# NODEMCU_ESP12.net
KiCad netlist of a schematic drawn in Altium Designer
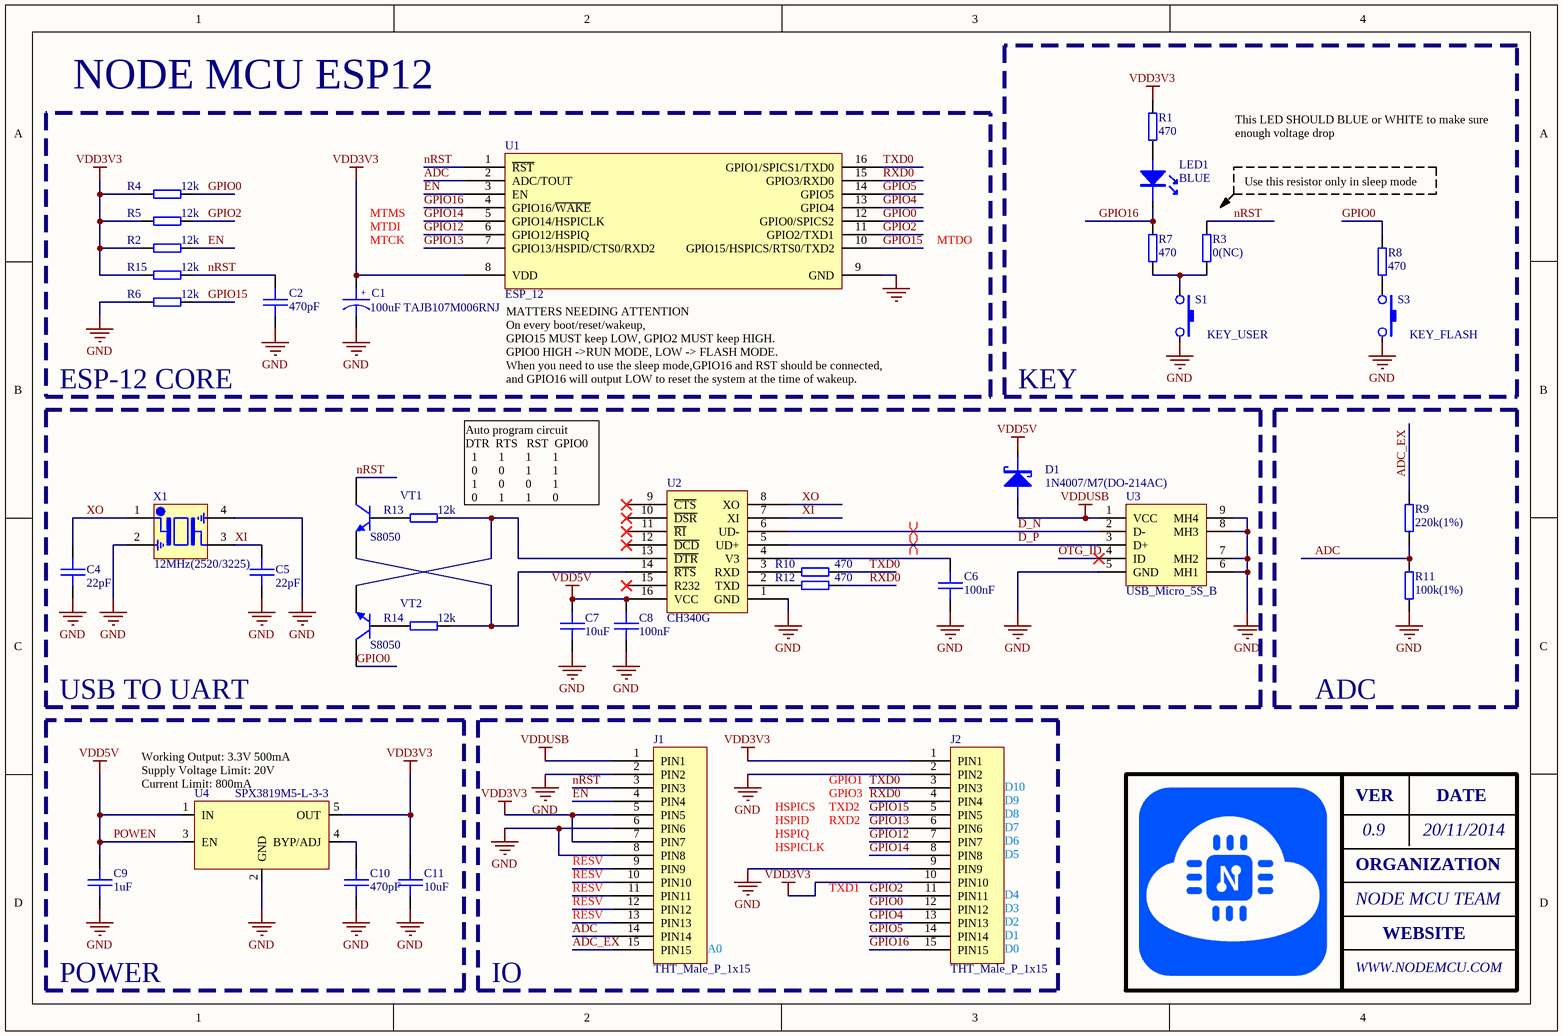
[diagram p0: NODEMCU_ESP12.SchDoc]

(export (version "E")
  (design (tool "Eeschema 10.0.6"))
  (components
    (comp (ref "C1")
      (value "100uF TAJB107M006RNJ")
      (footprint "SMT_C_Tantalum_B")
      (description "Capacitor, SM Tantalum; Body 3.5 x 2.8 mm (LxW typ)")
      (libsource (lib "Vowstar_Basic_Device") (part "SMT_C_Tantalum_B"))
    )
    (comp (ref "C2")
      (value "470pF")
      (footprint "SMT_C_0402")
      (description "Surface mount capacitor 0402")
      (libsource (lib "Vowstar_Basic_Device") (part "SMT_C_0402"))
    )
    (comp (ref "C4")
      (value "22pF")
      (footprint "SMT_C_0402")
      (description "Surface mount capacitor 0402")
      (libsource (lib "Vowstar_Basic_Device") (part "SMT_C_0402"))
    )
    (comp (ref "C5")
      (value "22pF")
      (footprint "SMT_C_0402")
      (description "Surface mount capacitor 0402")
      (libsource (lib "Vowstar_Basic_Device") (part "SMT_C_0402"))
    )
    (comp (ref "C6")
      (value "100nF")
      (footprint "SMT_C_0402")
      (description "Surface mount capacitor 0402")
      (libsource (lib "Vowstar_Basic_Device") (part "SMT_C_0402"))
    )
    (comp (ref "C7")
      (value "10uF")
      (footprint "SMT_C_0402")
      (description "Surface mount capacitor 0402")
      (libsource (lib "Vowstar_Basic_Device") (part "SMT_C_0402"))
    )
    (comp (ref "C8")
      (value "100nF")
      (footprint "SMT_C_0402")
      (description "Surface mount capacitor 0402")
      (libsource (lib "Vowstar_Basic_Device") (part "SMT_C_0402"))
    )
    (comp (ref "C9")
      (value "1uF")
      (footprint "SMT_C_0402")
      (description "Surface mount capacitor 0402")
      (libsource (lib "Vowstar_Basic_Device") (part "SMT_C_0402"))
    )
    (comp (ref "C10")
      (value "470pF")
      (footprint "SMT_C_0402")
      (description "Surface mount capacitor 0402")
      (libsource (lib "Vowstar_Basic_Device") (part "SMT_C_0402"))
    )
    (comp (ref "C11")
      (value "10uF")
      (footprint "SMT_C_0402")
      (description "Surface mount capacitor 0402")
      (libsource (lib "Vowstar_Basic_Device") (part "SMT_C_0402"))
    )
    (comp (ref "D1")
      (value "1N4007/M7(DO-214AC)")
      (footprint "SMT_DIODE_DO_214AC")
      (description "Surface mount schottky diode DO-214AC(SMA) Package")
      (libsource (lib "Vowstar_Basic_Device") (part "SMT_DIODE_SCHOTTKY_DO_214AC"))
    )
    (comp (ref "J1")
      (value "THT_Male_P_1x15")
      (footprint "THT_Male_P_1x15-2.54mm")
      (description "THT Male pin header strip 1x15")
      (libsource (lib "Vowstar_Connector") (part "THT_Male_P_1x15"))
    )
    (comp (ref "J2")
      (value "THT_Male_P_1x15")
      (footprint "THT_Male_P_1x15-2.54mm")
      (description "THT Male pin header strip 1x15")
      (libsource (lib "Vowstar_Connector") (part "THT_Male_P_1x15"))
    )
    (comp (ref "LED1")
      (value "BLUE")
      (footprint "SMT_LED_0603")
      (description "SMT LED")
      (libsource (lib "Vowstar_Basic_Device") (part "SMT_LED_0603"))
    )
    (comp (ref "R1")
      (value "470")
      (footprint "SMT_R_0402")
      (description "Surface mount resistor 0402")
      (libsource (lib "Vowstar_Basic_Device") (part "SMT_R_0402"))
    )
    (comp (ref "R2")
      (value "12k")
      (footprint "SMT_R_0402")
      (description "Surface mount resistor 0402")
      (libsource (lib "Vowstar_Basic_Device") (part "SMT_R_0402"))
    )
    (comp (ref "R3")
      (value "0(NC)")
      (footprint "SMT_R_0402")
      (description "Surface mount resistor 0402")
      (libsource (lib "Vowstar_Basic_Device") (part "SMT_R_0402"))
    )
    (comp (ref "R4")
      (value "12k")
      (footprint "SMT_R_0402")
      (description "Surface mount resistor 0402")
      (libsource (lib "Vowstar_Basic_Device") (part "SMT_R_0402"))
    )
    (comp (ref "R5")
      (value "12k")
      (footprint "SMT_R_0402")
      (description "Surface mount resistor 0402")
      (libsource (lib "Vowstar_Basic_Device") (part "SMT_R_0402"))
    )
    (comp (ref "R6")
      (value "12k")
      (footprint "SMT_R_0402")
      (description "Surface mount resistor 0402")
      (libsource (lib "Vowstar_Basic_Device") (part "SMT_R_0402"))
    )
    (comp (ref "R7")
      (value "470")
      (footprint "SMT_R_0402")
      (description "Surface mount resistor 0402")
      (libsource (lib "Vowstar_Basic_Device") (part "SMT_R_0402"))
    )
    (comp (ref "R8")
      (value "470")
      (footprint "SMT_R_0402")
      (description "Surface mount resistor 0402")
      (libsource (lib "Vowstar_Basic_Device") (part "SMT_R_0402"))
    )
    (comp (ref "R9")
      (value "220k(1%)")
      (footprint "SMT_R_0402")
      (description "Surface mount resistor 0402")
      (libsource (lib "Vowstar_Basic_Device") (part "SMT_R_0402"))
    )
    (comp (ref "R10")
      (value "470")
      (footprint "SMT_R_0402")
      (description "Surface mount resistor 0402")
      (libsource (lib "Vowstar_Basic_Device") (part "SMT_R_0402"))
    )
    (comp (ref "R11")
      (value "100k(1%)")
      (footprint "SMT_R_0402")
      (description "Surface mount resistor 0402")
      (libsource (lib "Vowstar_Basic_Device") (part "SMT_R_0402"))
    )
    (comp (ref "R12")
      (value "470")
      (footprint "SMT_R_0402")
      (description "Surface mount resistor 0402")
      (libsource (lib "Vowstar_Basic_Device") (part "SMT_R_0402"))
    )
    (comp (ref "R13")
      (value "12k")
      (footprint "SMT_R_0402")
      (description "Surface mount resistor 0402")
      (libsource (lib "Vowstar_Basic_Device") (part "SMT_R_0402"))
    )
    (comp (ref "R14")
      (value "12k")
      (footprint "SMT_R_0402")
      (description "Surface mount resistor 0402")
      (libsource (lib "Vowstar_Basic_Device") (part "SMT_R_0402"))
    )
    (comp (ref "R15")
      (value "12k")
      (footprint "SMT_R_0402")
      (description "Surface mount resistor 0402")
      (libsource (lib "Vowstar_Basic_Device") (part "SMT_R_0402"))
    )
    (comp (ref "S1")
      (value "KEY_USER")
      (footprint "SMT_SW_PTS_820")
      (description "SMT Tactile ‎Switch PTS 820 Series")
      (libsource (lib "Vowstar_Switch") (part "SMT_SW_PTS_820"))
    )
    (comp (ref "S3")
      (value "KEY_FLASH")
      (footprint "SMT_SW_PTS_820")
      (description "SMT Tactile ‎Switch PTS 820 Series")
      (libsource (lib "Vowstar_Switch") (part "SMT_SW_PTS_820"))
    )
    (comp (ref "U1")
      (value "ESP_12")
      (footprint "ESP_12")
      (description "ESP-12 Wi-Fi Module by AI-Thinker")
      (libsource (lib "Vowstar_Module") (part "ESP_12"))
    )
    (comp (ref "U2")
      (value "CH340G")
      (footprint "SOP-16")
      (description "CH340G USB to serial (UART) bridge")
      (libsource (lib "Vowstar_IC_General") (part "CH340G"))
    )
    (comp (ref "U3")
      (value "USB_Micro_5S_B")
      (footprint "USB_MICRO_5S_B")
      (description "USB micro female SMT with 4 fixed foot")
      (libsource (lib "Vowstar_Connector") (part "USB_Micro_5S_B"))
    )
    (comp (ref "U4")
      (value "SPX3819M5-L-3-3")
      (footprint "SOT23-5")
      (description "500mA, Low-Noise LDO Voltage Regulator")
      (libsource (lib "Vowstar_IC_General") (part "SPX3819"))
    )
    (comp (ref "VT1")
      (value "S8050")
      (footprint "SMT_TRIODE_NPN")
      (description "Surface mount NPN transistor, package SOT-23")
      (libsource (lib "Vowstar_Basic_Device") (part "SMT_TRIODE_NPN"))
    )
    (comp (ref "VT2")
      (value "S8050")
      (footprint "SMT_TRIODE_NPN")
      (description "Surface mount NPN transistor, package SOT-23")
      (libsource (lib "Vowstar_Basic_Device") (part "SMT_TRIODE_NPN"))
    )
    (comp (ref "X1")
      (value "12MHz(2520/3225)")
      (footprint "SMT_XTAL_2520")
      (description "Passive crystal")
      (libsource (lib "Vowstar_Basic_Device") (part "SMT_XTAL_PASSIVE"))
    )
  )
  (nets
    (net (code "1") (name "/ADC") (class "Default")
      (node (ref "J1") (pin "14") (pinfunction "PIN14_14") (pintype "passive"))
      (node (ref "R11") (pin "2") (pinfunction "2_2") (pintype "passive"))
      (node (ref "R9") (pin "1") (pinfunction "1_1") (pintype "passive"))
      (node (ref "U1") (pin "2") (pinfunction "ADC/TOUT_2") (pintype "passive"))
    )
    (net (code "2") (name "/ADC_EX") (class "Default")
      (node (ref "J1") (pin "15") (pinfunction "PIN15_15") (pintype "passive"))
      (node (ref "R9") (pin "2") (pinfunction "2_2") (pintype "passive"))
    )
    (net (code "3") (name "/D_N") (class "Default")
      (node (ref "U2") (pin "6") (pinfunction "UD-_6") (pintype "passive"))
      (node (ref "U3") (pin "2") (pinfunction "D-_2") (pintype "passive"))
    )
    (net (code "4") (name "/D_P") (class "Default")
      (node (ref "U2") (pin "5") (pinfunction "UD+_5") (pintype "passive"))
      (node (ref "U3") (pin "3") (pinfunction "D+_3") (pintype "passive"))
    )
    (net (code "5") (name "/EN") (class "Default")
      (node (ref "J1") (pin "4") (pinfunction "PIN4_4") (pintype "passive"))
      (node (ref "R2") (pin "2") (pinfunction "2_2") (pintype "passive"))
      (node (ref "U1") (pin "3") (pinfunction "EN_3") (pintype "passive"))
    )
    (net (code "6") (name "/GPIO0") (class "Default")
      (node (ref "J2") (pin "12") (pinfunction "PIN12_12") (pintype "passive"))
      (node (ref "R4") (pin "2") (pinfunction "2_2") (pintype "passive"))
      (node (ref "R8") (pin "2") (pinfunction "2_2") (pintype "passive"))
      (node (ref "U1") (pin "12") (pinfunction "GPIO0/SPICS2_12") (pintype "passive"))
      (node (ref "VT2") (pin "3") (pinfunction "C_3") (pintype "passive"))
    )
    (net (code "7") (name "/GPIO2") (class "Default")
      (node (ref "J2") (pin "11") (pinfunction "PIN11_11") (pintype "passive"))
      (node (ref "R5") (pin "2") (pinfunction "2_2") (pintype "passive"))
      (node (ref "U1") (pin "11") (pinfunction "GPIO2/TXD1_11") (pintype "passive"))
    )
    (net (code "8") (name "/GPIO4") (class "Default")
      (node (ref "J2") (pin "13") (pinfunction "PIN13_13") (pintype "passive"))
      (node (ref "U1") (pin "13") (pinfunction "GPIO4_13") (pintype "passive"))
    )
    (net (code "9") (name "/GPIO5") (class "Default")
      (node (ref "J2") (pin "14") (pinfunction "PIN14_14") (pintype "passive"))
      (node (ref "U1") (pin "14") (pinfunction "GPIO5_14") (pintype "passive"))
    )
    (net (code "10") (name "/GPIO12") (class "Default")
      (node (ref "J2") (pin "7") (pinfunction "PIN7_7") (pintype "passive"))
      (node (ref "U1") (pin "6") (pinfunction "GPIO12/HSPIQ_6") (pintype "passive"))
    )
    (net (code "11") (name "/GPIO13") (class "Default")
      (node (ref "J2") (pin "6") (pinfunction "PIN6_6") (pintype "passive"))
      (node (ref "U1") (pin "7") (pinfunction "GPIO13/HSPID/CTS0/RXD2_7") (pintype "passive"))
    )
    (net (code "12") (name "/GPIO14") (class "Default")
      (node (ref "J2") (pin "8") (pinfunction "PIN8_8") (pintype "passive"))
      (node (ref "U1") (pin "5") (pinfunction "GPIO14/HSPICLK_5") (pintype "passive"))
    )
    (net (code "13") (name "/GPIO15") (class "Default")
      (node (ref "J2") (pin "5") (pinfunction "PIN5_5") (pintype "passive"))
      (node (ref "R6") (pin "2") (pinfunction "2_2") (pintype "passive"))
      (node (ref "U1") (pin "10") (pinfunction "GPIO15/HSPICS/RTS0/TXD2_10") (pintype "passive"))
    )
    (net (code "14") (name "/GPIO16") (class "Default")
      (node (ref "J2") (pin "15") (pinfunction "PIN15_15") (pintype "passive"))
      (node (ref "LED1") (pin "2") (pinfunction "K_2") (pintype "passive"))
      (node (ref "R7") (pin "2") (pinfunction "2_2") (pintype "passive"))
      (node (ref "U1") (pin "4") (pinfunction "GPIO16/~{WAKE}_4") (pintype "passive"))
    )
    (net (code "15") (name "/OTG_ID") (class "Default")
      (node (ref "U3") (pin "4") (pinfunction "ID_4") (pintype "passive+no_connect"))
    )
    (net (code "16") (name "/RXD0") (class "Default")
      (node (ref "J2") (pin "4") (pinfunction "PIN4_4") (pintype "passive"))
      (node (ref "R12") (pin "1") (pinfunction "1_1") (pintype "passive"))
      (node (ref "U1") (pin "15") (pinfunction "GPIO3/RXD0_15") (pintype "passive"))
    )
    (net (code "17") (name "/TXD0") (class "Default")
      (node (ref "J2") (pin "3") (pinfunction "PIN3_3") (pintype "passive"))
      (node (ref "R10") (pin "1") (pinfunction "1_1") (pintype "passive"))
      (node (ref "U1") (pin "16") (pinfunction "GPIO1/SPICS1/TXD0_16") (pintype "passive"))
    )
    (net (code "18") (name "/XI") (class "Default")
      (node (ref "C5") (pin "1") (pinfunction "1_1") (pintype "passive"))
      (node (ref "U2") (pin "7") (pinfunction "XI_7") (pintype "passive"))
      (node (ref "X1") (pin "3") (pinfunction "IN/OUT_3") (pintype "passive"))
    )
    (net (code "19") (name "/XO") (class "Default")
      (node (ref "C4") (pin "1") (pinfunction "1_1") (pintype "passive"))
      (node (ref "U2") (pin "8") (pinfunction "XO_8") (pintype "passive"))
      (node (ref "X1") (pin "1") (pinfunction "IN/OUT_1") (pintype "passive"))
    )
    (net (code "20") (name "/nRST") (class "Default")
      (node (ref "C2") (pin "1") (pinfunction "1_1") (pintype "passive"))
      (node (ref "J1") (pin "3") (pinfunction "PIN3_3") (pintype "passive"))
      (node (ref "R15") (pin "2") (pinfunction "2_2") (pintype "passive"))
      (node (ref "R3") (pin "2") (pinfunction "2_2") (pintype "passive"))
      (node (ref "U1") (pin "1") (pinfunction "~{RST}_1") (pintype "passive"))
      (node (ref "VT1") (pin "3") (pinfunction "C_3") (pintype "passive"))
    )
    (net (code "21") (name "GND") (class "Default")
      (node (ref "C1") (pin "2") (pinfunction "2_2") (pintype "passive"))
      (node (ref "C10") (pin "2") (pinfunction "2_2") (pintype "passive"))
      (node (ref "C11") (pin "2") (pinfunction "2_2") (pintype "passive"))
      (node (ref "C2") (pin "2") (pinfunction "2_2") (pintype "passive"))
      (node (ref "C4") (pin "2") (pinfunction "2_2") (pintype "passive"))
      (node (ref "C5") (pin "2") (pinfunction "2_2") (pintype "passive"))
      (node (ref "C6") (pin "2") (pinfunction "2_2") (pintype "passive"))
      (node (ref "C7") (pin "2") (pinfunction "2_2") (pintype "passive"))
      (node (ref "C8") (pin "2") (pinfunction "2_2") (pintype "passive"))
      (node (ref "C9") (pin "2") (pinfunction "2_2") (pintype "passive"))
      (node (ref "J1") (pin "2") (pinfunction "PIN2_2") (pintype "passive"))
      (node (ref "J1") (pin "6") (pinfunction "PIN6_6") (pintype "passive"))
      (node (ref "J1") (pin "8") (pinfunction "PIN8_8") (pintype "passive"))
      (node (ref "J2") (pin "2") (pinfunction "PIN2_2") (pintype "passive"))
      (node (ref "J2") (pin "9") (pinfunction "PIN9_9") (pintype "passive"))
      (node (ref "R11") (pin "1") (pinfunction "1_1") (pintype "passive"))
      (node (ref "R6") (pin "1") (pinfunction "1_1") (pintype "passive"))
      (node (ref "S1") (pin "2") (pinfunction "2_2") (pintype "passive"))
      (node (ref "S3") (pin "2") (pinfunction "2_2") (pintype "passive"))
      (node (ref "U1") (pin "9") (pinfunction "GND_9") (pintype "passive"))
      (node (ref "U2") (pin "1") (pinfunction "GND_1") (pintype "passive"))
      (node (ref "U3") (pin "5") (pinfunction "GND_5") (pintype "passive"))
      (node (ref "U3") (pin "6") (pinfunction "MH1_6") (pintype "passive"))
      (node (ref "U3") (pin "7") (pinfunction "MH2_7") (pintype "passive"))
      (node (ref "U3") (pin "8") (pinfunction "MH3_8") (pintype "passive"))
      (node (ref "U3") (pin "9") (pinfunction "MH4_9") (pintype "passive"))
      (node (ref "U4") (pin "2") (pinfunction "GND_2") (pintype "passive"))
      (node (ref "X1") (pin "2") (pinfunction "GND_2") (pintype "passive"))
      (node (ref "X1") (pin "4") (pinfunction "GND_4") (pintype "passive"))
    )
    (net (code "22") (name "Net-(LED1-A)") (class "Default")
      (node (ref "LED1") (pin "1") (pinfunction "A_1") (pintype "passive"))
      (node (ref "R1") (pin "1") (pinfunction "1_1") (pintype "passive"))
    )
    (net (code "23") (name "Net-(R3-Pad1)") (class "Default")
      (node (ref "R3") (pin "1") (pinfunction "1_1") (pintype "passive"))
      (node (ref "R7") (pin "1") (pinfunction "1_1") (pintype "passive"))
      (node (ref "S1") (pin "1") (pinfunction "1_1") (pintype "passive"))
    )
    (net (code "24") (name "Net-(R8-Pad1)") (class "Default")
      (node (ref "R8") (pin "1") (pinfunction "1_1") (pintype "passive"))
      (node (ref "S3") (pin "1") (pinfunction "1_1") (pintype "passive"))
    )
    (net (code "25") (name "Net-(U2-RXD)") (class "Default")
      (node (ref "R10") (pin "2") (pinfunction "2_2") (pintype "passive"))
      (node (ref "U2") (pin "3") (pinfunction "RXD_3") (pintype "passive"))
    )
    (net (code "26") (name "Net-(U2-TXD)") (class "Default")
      (node (ref "R12") (pin "2") (pinfunction "2_2") (pintype "passive"))
      (node (ref "U2") (pin "2") (pinfunction "TXD_2") (pintype "passive"))
    )
    (net (code "27") (name "Net-(U2-V3)") (class "Default")
      (node (ref "C6") (pin "1") (pinfunction "1_1") (pintype "passive"))
      (node (ref "U2") (pin "4") (pinfunction "V3_4") (pintype "passive"))
    )
    (net (code "28") (name "Net-(U2-~{DTR})") (class "Default")
      (node (ref "R13") (pin "2") (pinfunction "2_2") (pintype "passive"))
      (node (ref "U2") (pin "13") (pinfunction "~{DTR}_13") (pintype "passive"))
      (node (ref "VT2") (pin "2") (pinfunction "E_2") (pintype "passive"))
    )
    (net (code "29") (name "Net-(U2-~{RTS})") (class "Default")
      (node (ref "R14") (pin "2") (pinfunction "2_2") (pintype "passive"))
      (node (ref "U2") (pin "14") (pinfunction "~{RTS}_14") (pintype "passive"))
      (node (ref "VT1") (pin "2") (pinfunction "E_2") (pintype "passive"))
    )
    (net (code "30") (name "Net-(U4-BYP{slash}ADJ)") (class "Default")
      (node (ref "C10") (pin "1") (pinfunction "1_1") (pintype "passive"))
      (node (ref "U4") (pin "4") (pinfunction "BYP/ADJ_4") (pintype "passive"))
    )
    (net (code "31") (name "Net-(VT1-B)") (class "Default")
      (node (ref "R13") (pin "1") (pinfunction "1_1") (pintype "passive"))
      (node (ref "VT1") (pin "1") (pinfunction "B_1") (pintype "passive"))
    )
    (net (code "32") (name "Net-(VT2-B)") (class "Default")
      (node (ref "R14") (pin "1") (pinfunction "1_1") (pintype "passive"))
      (node (ref "VT2") (pin "1") (pinfunction "B_1") (pintype "passive"))
    )
    (net (code "33") (name "VDD3V3") (class "Default")
      (node (ref "C1") (pin "1") (pinfunction "1_1") (pintype "passive"))
      (node (ref "C11") (pin "1") (pinfunction "1_1") (pintype "passive"))
      (node (ref "J1") (pin "5") (pinfunction "PIN5_5") (pintype "passive"))
      (node (ref "J1") (pin "7") (pinfunction "PIN7_7") (pintype "passive"))
      (node (ref "J2") (pin "1") (pinfunction "PIN1_1") (pintype "passive"))
      (node (ref "J2") (pin "10") (pinfunction "PIN10_10") (pintype "passive"))
      (node (ref "R1") (pin "2") (pinfunction "2_2") (pintype "passive"))
      (node (ref "R15") (pin "1") (pinfunction "1_1") (pintype "passive"))
      (node (ref "R2") (pin "1") (pinfunction "1_1") (pintype "passive"))
      (node (ref "R4") (pin "1") (pinfunction "1_1") (pintype "passive"))
      (node (ref "R5") (pin "1") (pinfunction "1_1") (pintype "passive"))
      (node (ref "U1") (pin "8") (pinfunction "VDD_8") (pintype "passive"))
      (node (ref "U4") (pin "5") (pinfunction "OUT_5") (pintype "passive"))
    )
    (net (code "34") (name "VDD5V") (class "Default")
      (node (ref "C7") (pin "1") (pinfunction "1_1") (pintype "passive"))
      (node (ref "C8") (pin "1") (pinfunction "1_1") (pintype "passive"))
      (node (ref "C9") (pin "1") (pinfunction "1_1") (pintype "passive"))
      (node (ref "D1") (pin "2") (pinfunction "K_2") (pintype "passive"))
      (node (ref "U2") (pin "16") (pinfunction "VCC_16") (pintype "passive"))
      (node (ref "U4") (pin "1") (pinfunction "IN_1") (pintype "passive"))
      (node (ref "U4") (pin "3") (pinfunction "EN_3") (pintype "passive"))
    )
    (net (code "35") (name "VDDUSB") (class "Default")
      (node (ref "D1") (pin "1") (pinfunction "A_1") (pintype "passive"))
      (node (ref "J1") (pin "1") (pinfunction "PIN1_1") (pintype "passive"))
      (node (ref "U3") (pin "1") (pinfunction "VCC_1") (pintype "passive"))
    )
    (net (code "36") (name "unconnected-(J1-PIN9-Pad9)") (class "Default")
      (node (ref "J1") (pin "9") (pinfunction "PIN9_9") (pintype "passive"))
    )
    (net (code "37") (name "unconnected-(J1-PIN10-Pad10)") (class "Default")
      (node (ref "J1") (pin "10") (pinfunction "PIN10_10") (pintype "passive"))
    )
    (net (code "38") (name "unconnected-(J1-PIN11-Pad11)") (class "Default")
      (node (ref "J1") (pin "11") (pinfunction "PIN11_11") (pintype "passive"))
    )
    (net (code "39") (name "unconnected-(J1-PIN12-Pad12)") (class "Default")
      (node (ref "J1") (pin "12") (pinfunction "PIN12_12") (pintype "passive"))
    )
    (net (code "40") (name "unconnected-(J1-PIN13-Pad13)") (class "Default")
      (node (ref "J1") (pin "13") (pinfunction "PIN13_13") (pintype "passive"))
    )
    (net (code "41") (name "unconnected-(U2-R232-Pad15)") (class "Default")
      (node (ref "U2") (pin "15") (pinfunction "R232_15") (pintype "passive+no_connect"))
    )
    (net (code "42") (name "unconnected-(U2-~{CTS}-Pad9)") (class "Default")
      (node (ref "U2") (pin "9") (pinfunction "~{CTS}_9") (pintype "passive+no_connect"))
    )
    (net (code "43") (name "unconnected-(U2-~{DCD}-Pad12)") (class "Default")
      (node (ref "U2") (pin "12") (pinfunction "~{DCD}_12") (pintype "passive+no_connect"))
    )
    (net (code "44") (name "unconnected-(U2-~{DSR}-Pad10)") (class "Default")
      (node (ref "U2") (pin "10") (pinfunction "~{DSR}_10") (pintype "passive+no_connect"))
    )
    (net (code "45") (name "unconnected-(U2-~{RI}-Pad11)") (class "Default")
      (node (ref "U2") (pin "11") (pinfunction "~{RI}_11") (pintype "passive+no_connect"))
    )
  )
)
